# ME433.net
KiCad netlist of a schematic drawn in EAGLE
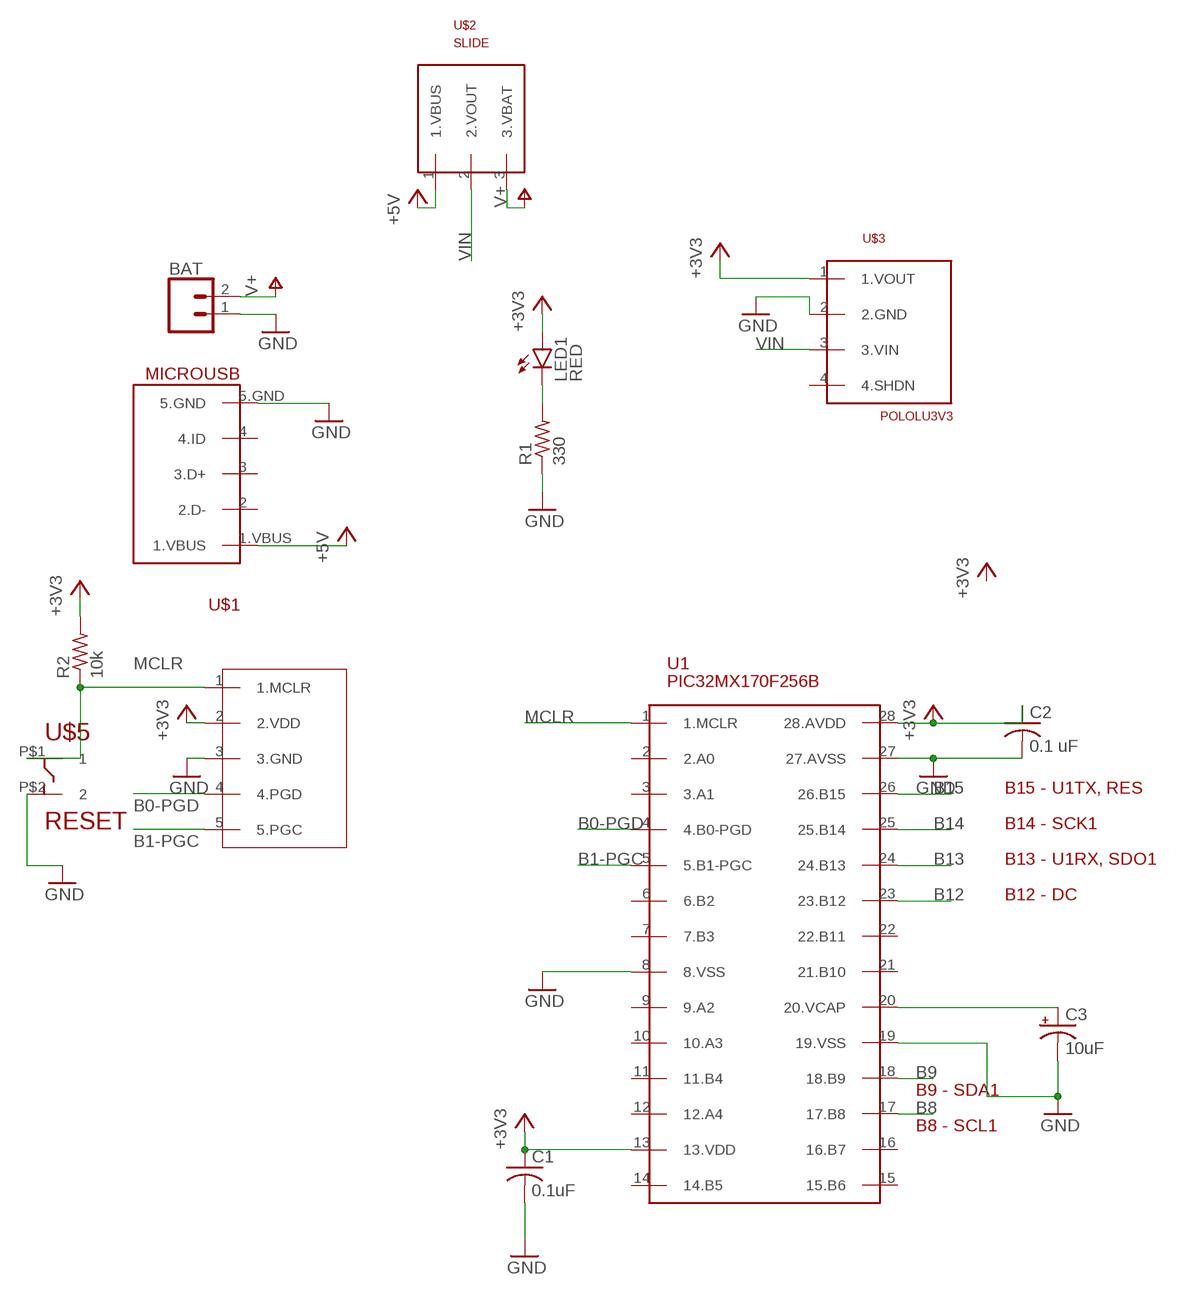
[diagram p0: schematic, sheet 1, part 1 of 2]
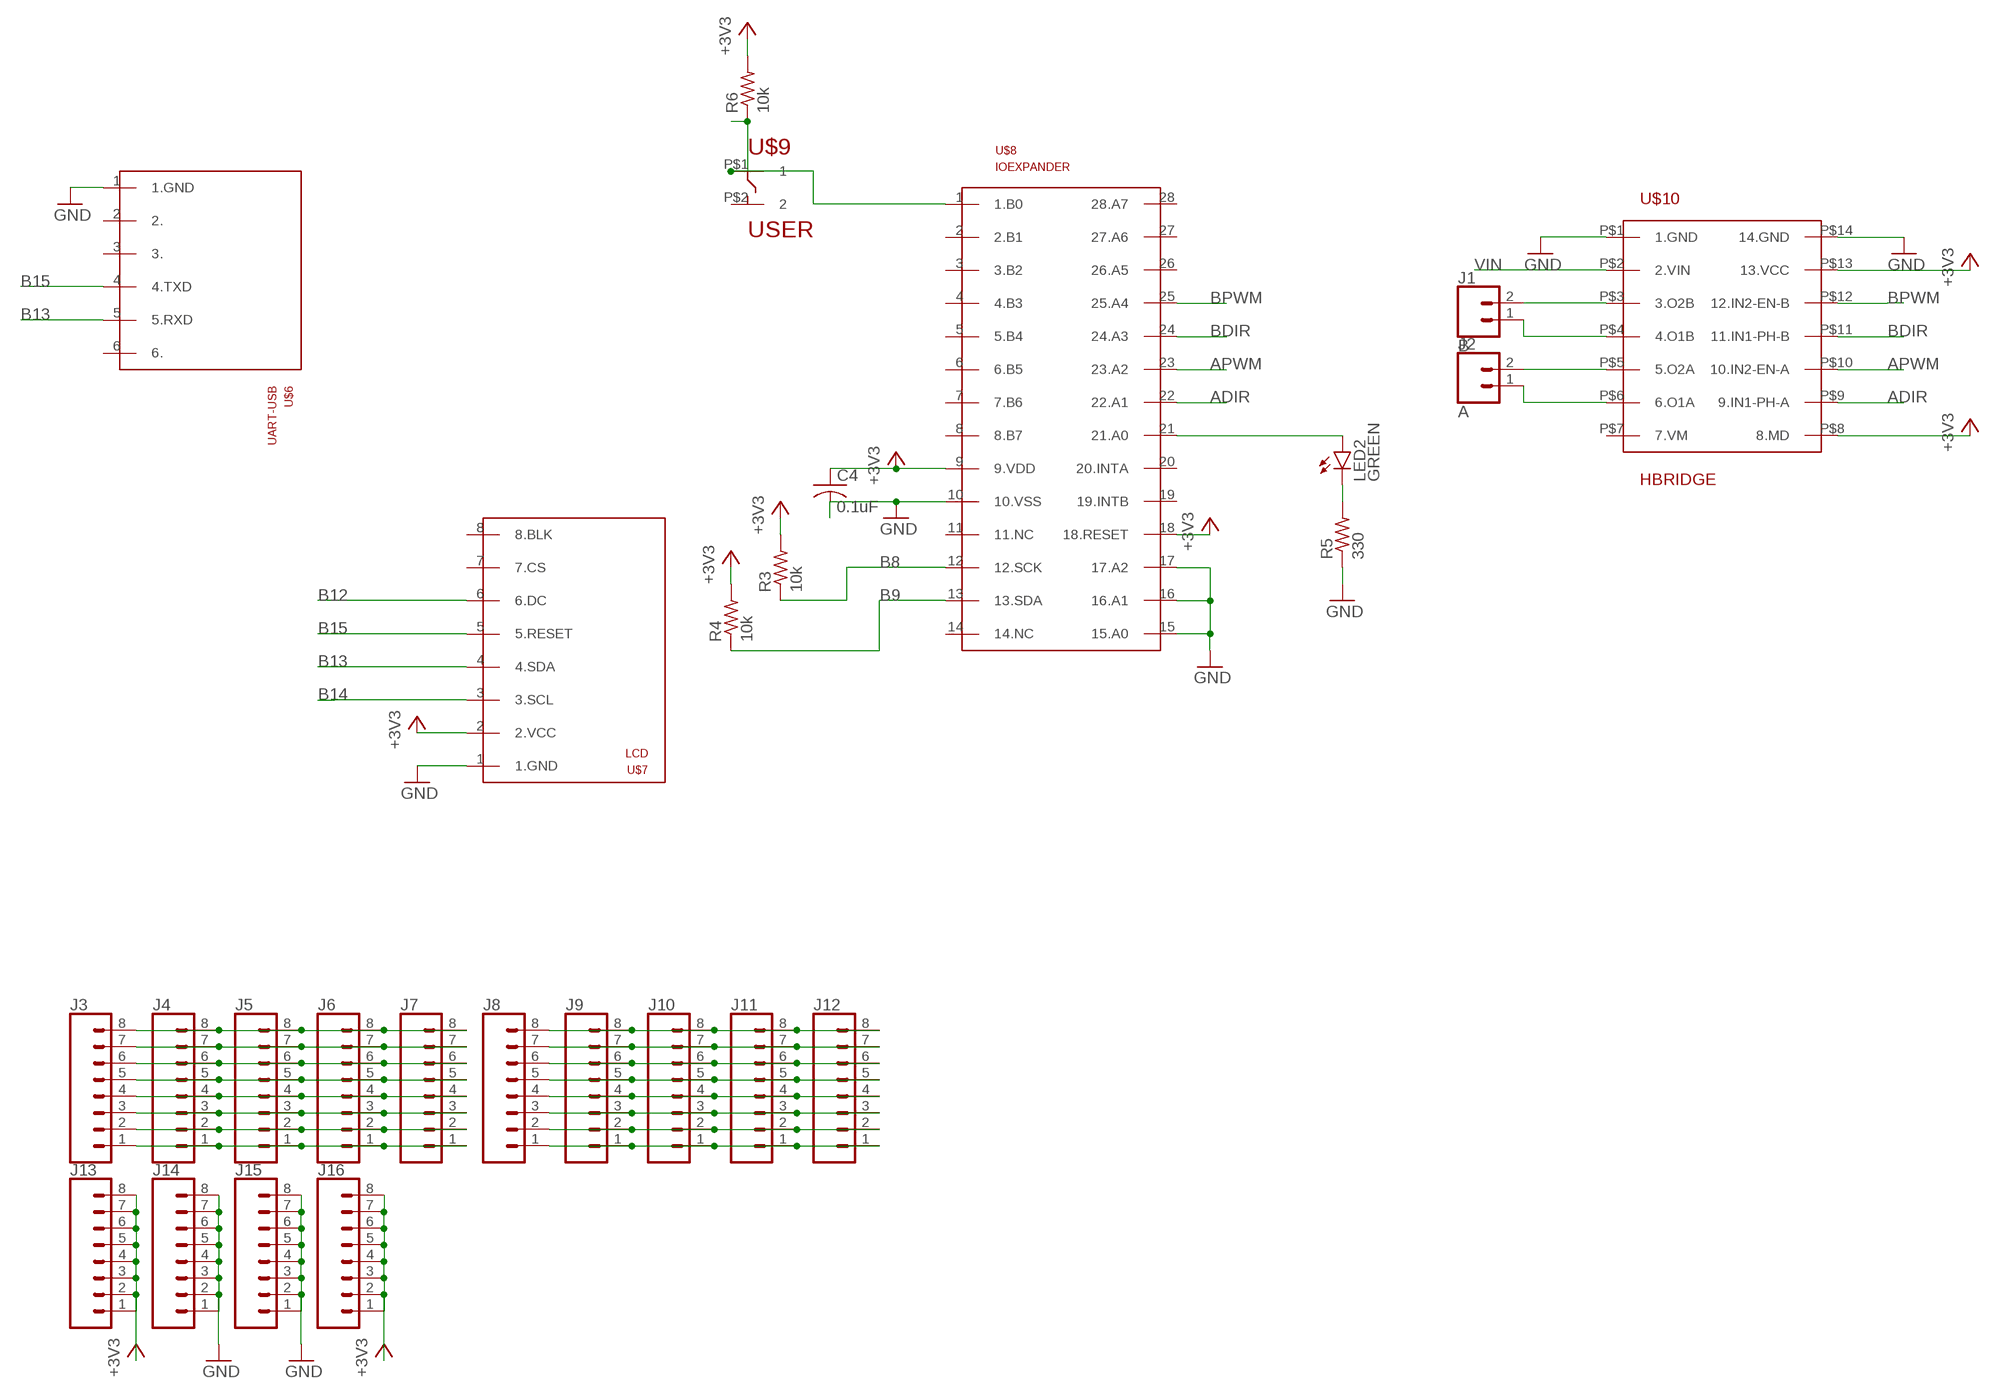
[diagram p1: schematic, sheet 1, part 2 of 2]

(export (version "E")
  (design (tool "Eeschema 10.0.6"))
  (components
    (comp (ref "BAT")
      (value "CONN_02")
      (footprint "eagle-import:1X02")
      (libsource (lib "eagle-import") (part "CONN_02"))
    )
    (comp (ref "C1")
      (value "0.1uF")
      (footprint "eagle-import:C025-030X050")
      (libsource (lib "eagle-import") (part "C-US025-030X050"))
    )
    (comp (ref "C2")
      (value "0.1 uF")
      (footprint "eagle-import:C025-030X050")
      (libsource (lib "eagle-import") (part "C-US025-030X050"))
    )
    (comp (ref "C3")
      (value "10uF")
      (footprint "eagle-import:B45181A")
      (libsource (lib "eagle-import") (part "CPOL-USB45181A"))
    )
    (comp (ref "C4")
      (value "0.1uF")
      (footprint "eagle-import:C025-030X050")
      (libsource (lib "eagle-import") (part "C-US025-030X050"))
    )
    (comp (ref "J1")
      (value "B")
      (footprint "eagle-import:1X02")
      (libsource (lib "eagle-import") (part "CONN_02"))
    )
    (comp (ref "J2")
      (value "A")
      (footprint "eagle-import:1X02")
      (libsource (lib "eagle-import") (part "CONN_02"))
    )
    (comp (ref "J3")
      (value "CONN_08\"")
      (footprint "eagle-import:1X08")
      (libsource (lib "eagle-import") (part "CONN_08{dblquote}"))
    )
    (comp (ref "J4")
      (value "CONN_08\"")
      (footprint "eagle-import:1X08")
      (libsource (lib "eagle-import") (part "CONN_08{dblquote}"))
    )
    (comp (ref "J5")
      (value "CONN_08\"")
      (footprint "eagle-import:1X08")
      (libsource (lib "eagle-import") (part "CONN_08{dblquote}"))
    )
    (comp (ref "J6")
      (value "CONN_08\"")
      (footprint "eagle-import:1X08")
      (libsource (lib "eagle-import") (part "CONN_08{dblquote}"))
    )
    (comp (ref "J7")
      (value "CONN_08\"")
      (footprint "eagle-import:1X08")
      (libsource (lib "eagle-import") (part "CONN_08{dblquote}"))
    )
    (comp (ref "J8")
      (value "CONN_08\"")
      (footprint "eagle-import:1X08")
      (libsource (lib "eagle-import") (part "CONN_08{dblquote}"))
    )
    (comp (ref "J9")
      (value "CONN_08\"")
      (footprint "eagle-import:1X08")
      (libsource (lib "eagle-import") (part "CONN_08{dblquote}"))
    )
    (comp (ref "J10")
      (value "CONN_08\"")
      (footprint "eagle-import:1X08")
      (libsource (lib "eagle-import") (part "CONN_08{dblquote}"))
    )
    (comp (ref "J11")
      (value "CONN_08\"")
      (footprint "eagle-import:1X08")
      (libsource (lib "eagle-import") (part "CONN_08{dblquote}"))
    )
    (comp (ref "J12")
      (value "CONN_08\"")
      (footprint "eagle-import:1X08")
      (libsource (lib "eagle-import") (part "CONN_08{dblquote}"))
    )
    (comp (ref "J13")
      (value "CONN_08\"")
      (footprint "eagle-import:1X08")
      (libsource (lib "eagle-import") (part "CONN_08{dblquote}"))
    )
    (comp (ref "J14")
      (value "CONN_08\"")
      (footprint "eagle-import:1X08")
      (libsource (lib "eagle-import") (part "CONN_08{dblquote}"))
    )
    (comp (ref "J15")
      (value "CONN_08\"")
      (footprint "eagle-import:1X08")
      (libsource (lib "eagle-import") (part "CONN_08{dblquote}"))
    )
    (comp (ref "J16")
      (value "CONN_08\"")
      (footprint "eagle-import:1X08")
      (libsource (lib "eagle-import") (part "CONN_08{dblquote}"))
    )
    (comp (ref "LED1")
      (value "RED")
      (footprint "eagle-import:LED3MM")
      (libsource (lib "eagle-import") (part "LED3MM"))
    )
    (comp (ref "LED2")
      (value "GREEN")
      (footprint "eagle-import:LED3MM")
      (libsource (lib "eagle-import") (part "LED3MM"))
    )
    (comp (ref "R1")
      (value "330")
      (footprint "eagle-import:0207_10")
      (libsource (lib "eagle-import") (part "R-US_0207/10"))
    )
    (comp (ref "R2")
      (value "10k")
      (footprint "eagle-import:0207_10")
      (libsource (lib "eagle-import") (part "R-US_0207/10"))
    )
    (comp (ref "R3")
      (value "10k")
      (footprint "eagle-import:0207_10")
      (libsource (lib "eagle-import") (part "R-US_0207/10"))
    )
    (comp (ref "R4")
      (value "10k")
      (footprint "eagle-import:0207_10")
      (libsource (lib "eagle-import") (part "R-US_0207/10"))
    )
    (comp (ref "R5")
      (value "330")
      (footprint "eagle-import:0207_10")
      (libsource (lib "eagle-import") (part "R-US_0207/10"))
    )
    (comp (ref "R6")
      (value "10k")
      (footprint "eagle-import:0207_10")
      (libsource (lib "eagle-import") (part "R-US_0207/10"))
    )
    (comp (ref "U$1")
      (value "MICROUSB")
      (footprint "eagle-import:MICROUSB")
      (libsource (lib "eagle-import") (part "MICROUSB"))
    )
    (comp (ref "U$2")
      (value "SLIDE")
      (footprint "eagle-import:SLIDE")
      (libsource (lib "eagle-import") (part "SLIDE"))
    )
    (comp (ref "U$3")
      (value "POLOLU3V3")
      (footprint "eagle-import:POLOLU3V3")
      (libsource (lib "eagle-import") (part "POLOLU3V3"))
    )
    (comp (ref "U$4")
      (value "SNAP")
      (footprint "eagle-import:SNAP")
      (libsource (lib "eagle-import") (part "SNAP"))
    )
    (comp (ref "U$5")
      (value "RESET")
      (footprint "eagle-import:PUSH")
      (libsource (lib "eagle-import") (part "PUSH"))
    )
    (comp (ref "U$6")
      (value "UART-USB")
      (footprint "eagle-import:UART-USB")
      (libsource (lib "eagle-import") (part "UART-USB"))
    )
    (comp (ref "U$7")
      (value "LCD")
      (footprint "eagle-import:LCD")
      (libsource (lib "eagle-import") (part "LCD"))
    )
    (comp (ref "U$8")
      (value "IOEXPANDER")
      (footprint "eagle-import:IOEXPANDER")
      (libsource (lib "eagle-import") (part "IOEXPANDER"))
    )
    (comp (ref "U$9")
      (value "USER")
      (footprint "eagle-import:PUSH")
      (libsource (lib "eagle-import") (part "PUSH"))
    )
    (comp (ref "U$10")
      (value "HBRIDGE")
      (footprint "eagle-import:HBRIDGE")
      (libsource (lib "eagle-import") (part "HBRIDGE"))
    )
    (comp (ref "U1")
      (value "PIC32MX170F256B")
      (footprint "eagle-import:DIL28-3")
      (libsource (lib "eagle-import") (part "PIC32MX170F256B"))
    )
  )
  (nets
    (net (code "1") (name "+3V3") (class "Default")
      (node (ref "C1") (pin "1") (pinfunction "1_1") (pintype "passive"))
      (node (ref "C2") (pin "1") (pinfunction "1_1") (pintype "passive"))
      (node (ref "C4") (pin "1") (pinfunction "1_1") (pintype "passive"))
      (node (ref "J13") (pin "1") (pinfunction "1_1") (pintype "passive"))
      (node (ref "J13") (pin "2") (pinfunction "2_2") (pintype "passive"))
      (node (ref "J13") (pin "3") (pinfunction "3_3") (pintype "passive"))
      (node (ref "J13") (pin "4") (pinfunction "4_4") (pintype "passive"))
      (node (ref "J13") (pin "5") (pinfunction "5_5") (pintype "passive"))
      (node (ref "J13") (pin "6") (pinfunction "6_6") (pintype "passive"))
      (node (ref "J13") (pin "7") (pinfunction "7_7") (pintype "passive"))
      (node (ref "J13") (pin "8") (pinfunction "8_8") (pintype "passive"))
      (node (ref "J16") (pin "1") (pinfunction "1_1") (pintype "passive"))
      (node (ref "J16") (pin "2") (pinfunction "2_2") (pintype "passive"))
      (node (ref "J16") (pin "3") (pinfunction "3_3") (pintype "passive"))
      (node (ref "J16") (pin "4") (pinfunction "4_4") (pintype "passive"))
      (node (ref "J16") (pin "5") (pinfunction "5_5") (pintype "passive"))
      (node (ref "J16") (pin "6") (pinfunction "6_6") (pintype "passive"))
      (node (ref "J16") (pin "7") (pinfunction "7_7") (pintype "passive"))
      (node (ref "J16") (pin "8") (pinfunction "8_8") (pintype "passive"))
      (node (ref "LED1") (pin "A") (pinfunction "A_A") (pintype "passive"))
      (node (ref "R2") (pin "2") (pinfunction "2_2") (pintype "passive"))
      (node (ref "R3") (pin "2") (pinfunction "2_2") (pintype "passive"))
      (node (ref "R4") (pin "2") (pinfunction "2_2") (pintype "passive"))
      (node (ref "R6") (pin "2") (pinfunction "2_2") (pintype "passive"))
      (node (ref "U$10") (pin "P$13") (pinfunction "13.VCC_P$13") (pintype "bidirectional"))
      (node (ref "U$10") (pin "P$8") (pinfunction "8.MD_P$8") (pintype "bidirectional"))
      (node (ref "U$3") (pin "1") (pinfunction "1.VOUT_1") (pintype "bidirectional"))
      (node (ref "U$4") (pin "2") (pinfunction "2.VDD_2") (pintype "bidirectional"))
      (node (ref "U$7") (pin "2") (pinfunction "2.VCC_2") (pintype "bidirectional"))
      (node (ref "U$8") (pin "18") (pinfunction "18.RESET_18") (pintype "bidirectional"))
      (node (ref "U$8") (pin "9") (pinfunction "9.VDD_9") (pintype "bidirectional"))
      (node (ref "U1") (pin "13") (pinfunction "13.VDD_13") (pintype "bidirectional"))
      (node (ref "U1") (pin "28") (pinfunction "28.AVDD_28") (pintype "bidirectional"))
    )
    (net (code "2") (name "+5V") (class "Default")
      (node (ref "U$1") (pin "1.VBUS") (pinfunction "1.VBUS_1.VBUS") (pintype "bidirectional"))
      (node (ref "U$2") (pin "1") (pinfunction "1.VBUS_1") (pintype "bidirectional"))
    )
    (net (code "3") (name "/ADIR") (class "Default")
      (node (ref "U$10") (pin "P$9") (pinfunction "9.IN1-PH-A_P$9") (pintype "bidirectional"))
      (node (ref "U$8") (pin "22") (pinfunction "22.A1_22") (pintype "bidirectional"))
    )
    (net (code "4") (name "/APWM") (class "Default")
      (node (ref "U$10") (pin "P$10") (pinfunction "10.IN2-EN-A_P$10") (pintype "bidirectional"))
      (node (ref "U$8") (pin "23") (pinfunction "23.A2_23") (pintype "bidirectional"))
    )
    (net (code "5") (name "/B0-PGD") (class "Default")
      (node (ref "U$4") (pin "4") (pinfunction "4.PGD_4") (pintype "bidirectional"))
      (node (ref "U1") (pin "4") (pinfunction "4.B0-PGD_4") (pintype "bidirectional"))
    )
    (net (code "6") (name "/B1-PGC") (class "Default")
      (node (ref "U$4") (pin "5") (pinfunction "5.PGC_5") (pintype "bidirectional"))
      (node (ref "U1") (pin "5") (pinfunction "5.B1-PGC_5") (pintype "bidirectional"))
    )
    (net (code "7") (name "/B8") (class "Default")
      (node (ref "R3") (pin "1") (pinfunction "1_1") (pintype "passive"))
      (node (ref "U$8") (pin "12") (pinfunction "12.SCK_12") (pintype "bidirectional"))
      (node (ref "U1") (pin "17") (pinfunction "17.B8_17") (pintype "bidirectional"))
    )
    (net (code "8") (name "/B9") (class "Default")
      (node (ref "R4") (pin "1") (pinfunction "1_1") (pintype "passive"))
      (node (ref "U$8") (pin "13") (pinfunction "13.SDA_13") (pintype "bidirectional"))
      (node (ref "U1") (pin "18") (pinfunction "18.B9_18") (pintype "bidirectional"))
    )
    (net (code "9") (name "/B12") (class "Default")
      (node (ref "U$7") (pin "6") (pinfunction "6.DC_6") (pintype "bidirectional"))
      (node (ref "U1") (pin "23") (pinfunction "23.B12_23") (pintype "bidirectional"))
    )
    (net (code "10") (name "/B13") (class "Default")
      (node (ref "U$6") (pin "5") (pinfunction "5.RXD_5") (pintype "bidirectional"))
      (node (ref "U$7") (pin "4") (pinfunction "4.SDA_4") (pintype "bidirectional"))
      (node (ref "U1") (pin "24") (pinfunction "24.B13_24") (pintype "bidirectional"))
    )
    (net (code "11") (name "/B14") (class "Default")
      (node (ref "U$7") (pin "3") (pinfunction "3.SCL_3") (pintype "bidirectional"))
      (node (ref "U1") (pin "25") (pinfunction "25.B14_25") (pintype "bidirectional"))
    )
    (net (code "12") (name "/B15") (class "Default")
      (node (ref "U$6") (pin "4") (pinfunction "4.TXD_4") (pintype "bidirectional"))
      (node (ref "U$7") (pin "5") (pinfunction "5.RESET_5") (pintype "bidirectional"))
      (node (ref "U1") (pin "26") (pinfunction "26.B15_26") (pintype "bidirectional"))
    )
    (net (code "13") (name "/BDIR") (class "Default")
      (node (ref "U$10") (pin "P$11") (pinfunction "11.IN1-PH-B_P$11") (pintype "bidirectional"))
      (node (ref "U$8") (pin "24") (pinfunction "24.A3_24") (pintype "bidirectional"))
    )
    (net (code "14") (name "/BPWM") (class "Default")
      (node (ref "U$10") (pin "P$12") (pinfunction "12.IN2-EN-B_P$12") (pintype "bidirectional"))
      (node (ref "U$8") (pin "25") (pinfunction "25.A4_25") (pintype "bidirectional"))
    )
    (net (code "15") (name "/MCLR") (class "Default")
      (node (ref "R2") (pin "1") (pinfunction "1_1") (pintype "passive"))
      (node (ref "U$4") (pin "1") (pinfunction "1.MCLR_1") (pintype "bidirectional"))
      (node (ref "U$5") (pin "P$1") (pinfunction "1_P$1") (pintype "bidirectional"))
      (node (ref "U1") (pin "1") (pinfunction "1.MCLR_1") (pintype "bidirectional"))
    )
    (net (code "16") (name "/VIN") (class "Default")
      (node (ref "U$10") (pin "P$2") (pinfunction "2.VIN_P$2") (pintype "bidirectional"))
      (node (ref "U$2") (pin "2") (pinfunction "2.VOUT_2") (pintype "bidirectional"))
      (node (ref "U$3") (pin "3") (pinfunction "3.VIN_3") (pintype "bidirectional"))
    )
    (net (code "17") (name "GND") (class "Default")
      (node (ref "BAT") (pin "1") (pinfunction "1_1") (pintype "passive"))
      (node (ref "C1") (pin "2") (pinfunction "2_2") (pintype "passive"))
      (node (ref "C2") (pin "2") (pinfunction "2_2") (pintype "passive"))
      (node (ref "C3") (pin "-") (pinfunction "-_-") (pintype "passive"))
      (node (ref "C4") (pin "2") (pinfunction "2_2") (pintype "passive"))
      (node (ref "J14") (pin "1") (pinfunction "1_1") (pintype "passive"))
      (node (ref "J14") (pin "2") (pinfunction "2_2") (pintype "passive"))
      (node (ref "J14") (pin "3") (pinfunction "3_3") (pintype "passive"))
      (node (ref "J14") (pin "4") (pinfunction "4_4") (pintype "passive"))
      (node (ref "J14") (pin "5") (pinfunction "5_5") (pintype "passive"))
      (node (ref "J14") (pin "6") (pinfunction "6_6") (pintype "passive"))
      (node (ref "J14") (pin "7") (pinfunction "7_7") (pintype "passive"))
      (node (ref "J14") (pin "8") (pinfunction "8_8") (pintype "passive"))
      (node (ref "J15") (pin "1") (pinfunction "1_1") (pintype "passive"))
      (node (ref "J15") (pin "2") (pinfunction "2_2") (pintype "passive"))
      (node (ref "J15") (pin "3") (pinfunction "3_3") (pintype "passive"))
      (node (ref "J15") (pin "4") (pinfunction "4_4") (pintype "passive"))
      (node (ref "J15") (pin "5") (pinfunction "5_5") (pintype "passive"))
      (node (ref "J15") (pin "6") (pinfunction "6_6") (pintype "passive"))
      (node (ref "J15") (pin "7") (pinfunction "7_7") (pintype "passive"))
      (node (ref "J15") (pin "8") (pinfunction "8_8") (pintype "passive"))
      (node (ref "R1") (pin "1") (pinfunction "1_1") (pintype "passive"))
      (node (ref "R5") (pin "1") (pinfunction "1_1") (pintype "passive"))
      (node (ref "U$1") (pin "5.GND") (pinfunction "5.GND_5.GND") (pintype "bidirectional"))
      (node (ref "U$10") (pin "P$1") (pinfunction "1.GND_P$1") (pintype "bidirectional"))
      (node (ref "U$10") (pin "P$14") (pinfunction "14.GND_P$14") (pintype "bidirectional"))
      (node (ref "U$3") (pin "2") (pinfunction "2.GND_2") (pintype "bidirectional"))
      (node (ref "U$4") (pin "3") (pinfunction "3.GND_3") (pintype "bidirectional"))
      (node (ref "U$5") (pin "P$2") (pinfunction "2_P$2") (pintype "bidirectional"))
      (node (ref "U$6") (pin "1") (pinfunction "1.GND_1") (pintype "bidirectional"))
      (node (ref "U$7") (pin "1") (pinfunction "1.GND_1") (pintype "bidirectional"))
      (node (ref "U$8") (pin "10") (pinfunction "10.VSS_10") (pintype "bidirectional"))
      (node (ref "U$8") (pin "15") (pinfunction "15.A0_15") (pintype "bidirectional"))
      (node (ref "U$8") (pin "16") (pinfunction "16.A1_16") (pintype "bidirectional"))
      (node (ref "U$8") (pin "17") (pinfunction "17.A2_17") (pintype "bidirectional"))
      (node (ref "U1") (pin "19") (pinfunction "19.VSS_19") (pintype "bidirectional"))
      (node (ref "U1") (pin "27") (pinfunction "27.AVSS_27") (pintype "bidirectional"))
      (node (ref "U1") (pin "8") (pinfunction "8.VSS_8") (pintype "bidirectional"))
    )
    (net (code "18") (name "Net-(J3-Pad1)") (class "Default")
      (node (ref "J3") (pin "1") (pinfunction "1_1") (pintype "passive"))
      (node (ref "J4") (pin "1") (pinfunction "1_1") (pintype "passive"))
      (node (ref "J5") (pin "1") (pinfunction "1_1") (pintype "passive"))
      (node (ref "J6") (pin "1") (pinfunction "1_1") (pintype "passive"))
      (node (ref "J7") (pin "1") (pinfunction "1_1") (pintype "passive"))
    )
    (net (code "19") (name "Net-(J3-Pad2)") (class "Default")
      (node (ref "J3") (pin "2") (pinfunction "2_2") (pintype "passive"))
      (node (ref "J4") (pin "2") (pinfunction "2_2") (pintype "passive"))
      (node (ref "J5") (pin "2") (pinfunction "2_2") (pintype "passive"))
      (node (ref "J6") (pin "2") (pinfunction "2_2") (pintype "passive"))
      (node (ref "J7") (pin "2") (pinfunction "2_2") (pintype "passive"))
    )
    (net (code "20") (name "Net-(J3-Pad3)") (class "Default")
      (node (ref "J3") (pin "3") (pinfunction "3_3") (pintype "passive"))
      (node (ref "J4") (pin "3") (pinfunction "3_3") (pintype "passive"))
      (node (ref "J5") (pin "3") (pinfunction "3_3") (pintype "passive"))
      (node (ref "J6") (pin "3") (pinfunction "3_3") (pintype "passive"))
      (node (ref "J7") (pin "3") (pinfunction "3_3") (pintype "passive"))
    )
    (net (code "21") (name "Net-(J3-Pad4)") (class "Default")
      (node (ref "J3") (pin "4") (pinfunction "4_4") (pintype "passive"))
      (node (ref "J4") (pin "4") (pinfunction "4_4") (pintype "passive"))
      (node (ref "J5") (pin "4") (pinfunction "4_4") (pintype "passive"))
      (node (ref "J6") (pin "4") (pinfunction "4_4") (pintype "passive"))
      (node (ref "J7") (pin "4") (pinfunction "4_4") (pintype "passive"))
    )
    (net (code "22") (name "Net-(J3-Pad5)") (class "Default")
      (node (ref "J3") (pin "5") (pinfunction "5_5") (pintype "passive"))
      (node (ref "J4") (pin "5") (pinfunction "5_5") (pintype "passive"))
      (node (ref "J5") (pin "5") (pinfunction "5_5") (pintype "passive"))
      (node (ref "J6") (pin "5") (pinfunction "5_5") (pintype "passive"))
      (node (ref "J7") (pin "5") (pinfunction "5_5") (pintype "passive"))
    )
    (net (code "23") (name "Net-(J3-Pad6)") (class "Default")
      (node (ref "J3") (pin "6") (pinfunction "6_6") (pintype "passive"))
      (node (ref "J4") (pin "6") (pinfunction "6_6") (pintype "passive"))
      (node (ref "J5") (pin "6") (pinfunction "6_6") (pintype "passive"))
      (node (ref "J6") (pin "6") (pinfunction "6_6") (pintype "passive"))
      (node (ref "J7") (pin "6") (pinfunction "6_6") (pintype "passive"))
    )
    (net (code "24") (name "Net-(J3-Pad7)") (class "Default")
      (node (ref "J3") (pin "7") (pinfunction "7_7") (pintype "passive"))
      (node (ref "J4") (pin "7") (pinfunction "7_7") (pintype "passive"))
      (node (ref "J5") (pin "7") (pinfunction "7_7") (pintype "passive"))
      (node (ref "J6") (pin "7") (pinfunction "7_7") (pintype "passive"))
      (node (ref "J7") (pin "7") (pinfunction "7_7") (pintype "passive"))
    )
    (net (code "25") (name "Net-(J3-Pad8)") (class "Default")
      (node (ref "J3") (pin "8") (pinfunction "8_8") (pintype "passive"))
      (node (ref "J4") (pin "8") (pinfunction "8_8") (pintype "passive"))
      (node (ref "J5") (pin "8") (pinfunction "8_8") (pintype "passive"))
      (node (ref "J6") (pin "8") (pinfunction "8_8") (pintype "passive"))
      (node (ref "J7") (pin "8") (pinfunction "8_8") (pintype "passive"))
    )
    (net (code "26") (name "Net-(J10-Pad1)") (class "Default")
      (node (ref "J10") (pin "1") (pinfunction "1_1") (pintype "passive"))
      (node (ref "J11") (pin "1") (pinfunction "1_1") (pintype "passive"))
      (node (ref "J12") (pin "1") (pinfunction "1_1") (pintype "passive"))
      (node (ref "J8") (pin "1") (pinfunction "1_1") (pintype "passive"))
      (node (ref "J9") (pin "1") (pinfunction "1_1") (pintype "passive"))
    )
    (net (code "27") (name "Net-(J10-Pad2)") (class "Default")
      (node (ref "J10") (pin "2") (pinfunction "2_2") (pintype "passive"))
      (node (ref "J11") (pin "2") (pinfunction "2_2") (pintype "passive"))
      (node (ref "J12") (pin "2") (pinfunction "2_2") (pintype "passive"))
      (node (ref "J8") (pin "2") (pinfunction "2_2") (pintype "passive"))
      (node (ref "J9") (pin "2") (pinfunction "2_2") (pintype "passive"))
    )
    (net (code "28") (name "Net-(J10-Pad3)") (class "Default")
      (node (ref "J10") (pin "3") (pinfunction "3_3") (pintype "passive"))
      (node (ref "J11") (pin "3") (pinfunction "3_3") (pintype "passive"))
      (node (ref "J12") (pin "3") (pinfunction "3_3") (pintype "passive"))
      (node (ref "J8") (pin "3") (pinfunction "3_3") (pintype "passive"))
      (node (ref "J9") (pin "3") (pinfunction "3_3") (pintype "passive"))
    )
    (net (code "29") (name "Net-(J10-Pad4)") (class "Default")
      (node (ref "J10") (pin "4") (pinfunction "4_4") (pintype "passive"))
      (node (ref "J11") (pin "4") (pinfunction "4_4") (pintype "passive"))
      (node (ref "J12") (pin "4") (pinfunction "4_4") (pintype "passive"))
      (node (ref "J8") (pin "4") (pinfunction "4_4") (pintype "passive"))
      (node (ref "J9") (pin "4") (pinfunction "4_4") (pintype "passive"))
    )
    (net (code "30") (name "Net-(J10-Pad5)") (class "Default")
      (node (ref "J10") (pin "5") (pinfunction "5_5") (pintype "passive"))
      (node (ref "J11") (pin "5") (pinfunction "5_5") (pintype "passive"))
      (node (ref "J12") (pin "5") (pinfunction "5_5") (pintype "passive"))
      (node (ref "J8") (pin "5") (pinfunction "5_5") (pintype "passive"))
      (node (ref "J9") (pin "5") (pinfunction "5_5") (pintype "passive"))
    )
    (net (code "31") (name "Net-(J10-Pad6)") (class "Default")
      (node (ref "J10") (pin "6") (pinfunction "6_6") (pintype "passive"))
      (node (ref "J11") (pin "6") (pinfunction "6_6") (pintype "passive"))
      (node (ref "J12") (pin "6") (pinfunction "6_6") (pintype "passive"))
      (node (ref "J8") (pin "6") (pinfunction "6_6") (pintype "passive"))
      (node (ref "J9") (pin "6") (pinfunction "6_6") (pintype "passive"))
    )
    (net (code "32") (name "Net-(J10-Pad7)") (class "Default")
      (node (ref "J10") (pin "7") (pinfunction "7_7") (pintype "passive"))
      (node (ref "J11") (pin "7") (pinfunction "7_7") (pintype "passive"))
      (node (ref "J12") (pin "7") (pinfunction "7_7") (pintype "passive"))
      (node (ref "J8") (pin "7") (pinfunction "7_7") (pintype "passive"))
      (node (ref "J9") (pin "7") (pinfunction "7_7") (pintype "passive"))
    )
    (net (code "33") (name "Net-(J10-Pad8)") (class "Default")
      (node (ref "J10") (pin "8") (pinfunction "8_8") (pintype "passive"))
      (node (ref "J11") (pin "8") (pinfunction "8_8") (pintype "passive"))
      (node (ref "J12") (pin "8") (pinfunction "8_8") (pintype "passive"))
      (node (ref "J8") (pin "8") (pinfunction "8_8") (pintype "passive"))
      (node (ref "J9") (pin "8") (pinfunction "8_8") (pintype "passive"))
    )
    (net (code "34") (name "Net-(LED1-C)") (class "Default")
      (node (ref "LED1") (pin "K") (pinfunction "C_K") (pintype "passive"))
      (node (ref "R1") (pin "2") (pinfunction "2_2") (pintype "passive"))
    )
    (net (code "35") (name "Net-(LED2-C)") (class "Default")
      (node (ref "LED2") (pin "K") (pinfunction "C_K") (pintype "passive"))
      (node (ref "R5") (pin "2") (pinfunction "2_2") (pintype "passive"))
    )
    (net (code "36") (name "Net-(U$8-1.B0)") (class "Default")
      (node (ref "R6") (pin "1") (pinfunction "1_1") (pintype "passive"))
      (node (ref "U$8") (pin "1") (pinfunction "1.B0_1") (pintype "bidirectional"))
      (node (ref "U$9") (pin "P$1") (pinfunction "1_P$1") (pintype "bidirectional"))
    )
    (net (code "37") (name "Net-(U$8-21.A0)") (class "Default")
      (node (ref "LED2") (pin "A") (pinfunction "A_A") (pintype "passive"))
      (node (ref "U$8") (pin "21") (pinfunction "21.A0_21") (pintype "bidirectional"))
    )
    (net (code "38") (name "Net-(U$10-3.O2B)") (class "Default")
      (node (ref "J1") (pin "2") (pinfunction "2_2") (pintype "passive"))
      (node (ref "U$10") (pin "P$3") (pinfunction "3.O2B_P$3") (pintype "bidirectional"))
    )
    (net (code "39") (name "Net-(U$10-4.O1B)") (class "Default")
      (node (ref "J1") (pin "1") (pinfunction "1_1") (pintype "passive"))
      (node (ref "U$10") (pin "P$4") (pinfunction "4.O1B_P$4") (pintype "bidirectional"))
    )
    (net (code "40") (name "Net-(U$10-5.O2A)") (class "Default")
      (node (ref "J2") (pin "2") (pinfunction "2_2") (pintype "passive"))
      (node (ref "U$10") (pin "P$5") (pinfunction "5.O2A_P$5") (pintype "bidirectional"))
    )
    (net (code "41") (name "Net-(U$10-6.O1A)") (class "Default")
      (node (ref "J2") (pin "1") (pinfunction "1_1") (pintype "passive"))
      (node (ref "U$10") (pin "P$6") (pinfunction "6.O1A_P$6") (pintype "bidirectional"))
    )
    (net (code "42") (name "Net-(U1-20.VCAP)") (class "Default")
      (node (ref "C3") (pin "+") (pinfunction "+_+") (pintype "passive"))
      (node (ref "U1") (pin "20") (pinfunction "20.VCAP_20") (pintype "bidirectional"))
    )
    (net (code "43") (name "V+") (class "Default")
      (node (ref "BAT") (pin "2") (pinfunction "2_2") (pintype "passive"))
      (node (ref "U$2") (pin "3") (pinfunction "3.VBAT_3") (pintype "bidirectional"))
    )
    (net (code "44") (name "unconnected-(U$1-2.D--Pad2)") (class "Default")
      (node (ref "U$1") (pin "2") (pinfunction "2.D-_2") (pintype "bidirectional"))
    )
    (net (code "45") (name "unconnected-(U$1-3.D+-Pad3)") (class "Default")
      (node (ref "U$1") (pin "3") (pinfunction "3.D+_3") (pintype "bidirectional"))
    )
    (net (code "46") (name "unconnected-(U$1-4.ID-Pad4)") (class "Default")
      (node (ref "U$1") (pin "4") (pinfunction "4.ID_4") (pintype "bidirectional"))
    )
    (net (code "47") (name "unconnected-(U$3-4.SHDN-Pad4)") (class "Default")
      (node (ref "U$3") (pin "4") (pinfunction "4.SHDN_4") (pintype "bidirectional"))
    )
    (net (code "48") (name "unconnected-(U$6-2.-Pad2)") (class "Default")
      (node (ref "U$6") (pin "2") (pinfunction "2._2") (pintype "bidirectional"))
    )
    (net (code "49") (name "unconnected-(U$6-3.-Pad3)") (class "Default")
      (node (ref "U$6") (pin "3") (pinfunction "3._3") (pintype "bidirectional"))
    )
    (net (code "50") (name "unconnected-(U$6-6.-Pad6)") (class "Default")
      (node (ref "U$6") (pin "6") (pinfunction "6._6") (pintype "bidirectional"))
    )
    (net (code "51") (name "unconnected-(U$7-7.CS-Pad7)") (class "Default")
      (node (ref "U$7") (pin "7") (pinfunction "7.CS_7") (pintype "bidirectional"))
    )
    (net (code "52") (name "unconnected-(U$7-8.BLK-Pad8)") (class "Default")
      (node (ref "U$7") (pin "8") (pinfunction "8.BLK_8") (pintype "bidirectional"))
    )
    (net (code "53") (name "unconnected-(U$8-2.B1-Pad2)") (class "Default")
      (node (ref "U$8") (pin "2") (pinfunction "2.B1_2") (pintype "bidirectional"))
    )
    (net (code "54") (name "unconnected-(U$8-3.B2-Pad3)") (class "Default")
      (node (ref "U$8") (pin "3") (pinfunction "3.B2_3") (pintype "bidirectional"))
    )
    (net (code "55") (name "unconnected-(U$8-4.B3-Pad4)") (class "Default")
      (node (ref "U$8") (pin "4") (pinfunction "4.B3_4") (pintype "bidirectional"))
    )
    (net (code "56") (name "unconnected-(U$8-5.B4-Pad5)") (class "Default")
      (node (ref "U$8") (pin "5") (pinfunction "5.B4_5") (pintype "bidirectional"))
    )
    (net (code "57") (name "unconnected-(U$8-6.B5-Pad6)") (class "Default")
      (node (ref "U$8") (pin "6") (pinfunction "6.B5_6") (pintype "bidirectional"))
    )
    (net (code "58") (name "unconnected-(U$8-7.B6-Pad7)") (class "Default")
      (node (ref "U$8") (pin "7") (pinfunction "7.B6_7") (pintype "bidirectional"))
    )
    (net (code "59") (name "unconnected-(U$8-8.B7-Pad8)") (class "Default")
      (node (ref "U$8") (pin "8") (pinfunction "8.B7_8") (pintype "bidirectional"))
    )
    (net (code "60") (name "unconnected-(U$8-11.NC-Pad11)") (class "Default")
      (node (ref "U$8") (pin "11") (pinfunction "11.NC_11") (pintype "bidirectional"))
    )
    (net (code "61") (name "unconnected-(U$8-14.NC-Pad14)") (class "Default")
      (node (ref "U$8") (pin "14") (pinfunction "14.NC_14") (pintype "bidirectional"))
    )
    (net (code "62") (name "unconnected-(U$8-19.INTB-Pad19)") (class "Default")
      (node (ref "U$8") (pin "19") (pinfunction "19.INTB_19") (pintype "bidirectional"))
    )
    (net (code "63") (name "unconnected-(U$8-20.INTA-Pad20)") (class "Default")
      (node (ref "U$8") (pin "20") (pinfunction "20.INTA_20") (pintype "bidirectional"))
    )
    (net (code "64") (name "unconnected-(U$8-26.A5-Pad26)") (class "Default")
      (node (ref "U$8") (pin "26") (pinfunction "26.A5_26") (pintype "bidirectional"))
    )
    (net (code "65") (name "unconnected-(U$8-27.A6-Pad27)") (class "Default")
      (node (ref "U$8") (pin "27") (pinfunction "27.A6_27") (pintype "bidirectional"))
    )
    (net (code "66") (name "unconnected-(U$8-28.A7-Pad28)") (class "Default")
      (node (ref "U$8") (pin "28") (pinfunction "28.A7_28") (pintype "bidirectional"))
    )
    (net (code "67") (name "unconnected-(U$9-2-PadP$2)") (class "Default")
      (node (ref "U$9") (pin "P$2") (pinfunction "2_P$2") (pintype "bidirectional"))
    )
    (net (code "68") (name "unconnected-(U$10-7.VM-PadP$7)") (class "Default")
      (node (ref "U$10") (pin "P$7") (pinfunction "7.VM_P$7") (pintype "bidirectional"))
    )
    (net (code "69") (name "unconnected-(U1-2.A0-Pad2)") (class "Default")
      (node (ref "U1") (pin "2") (pinfunction "2.A0_2") (pintype "bidirectional"))
    )
    (net (code "70") (name "unconnected-(U1-3.A1-Pad3)") (class "Default")
      (node (ref "U1") (pin "3") (pinfunction "3.A1_3") (pintype "bidirectional"))
    )
    (net (code "71") (name "unconnected-(U1-6.B2-Pad6)") (class "Default")
      (node (ref "U1") (pin "6") (pinfunction "6.B2_6") (pintype "bidirectional"))
    )
    (net (code "72") (name "unconnected-(U1-7.B3-Pad7)") (class "Default")
      (node (ref "U1") (pin "7") (pinfunction "7.B3_7") (pintype "bidirectional"))
    )
    (net (code "73") (name "unconnected-(U1-9.A2-Pad9)") (class "Default")
      (node (ref "U1") (pin "9") (pinfunction "9.A2_9") (pintype "bidirectional"))
    )
    (net (code "74") (name "unconnected-(U1-10.A3-Pad10)") (class "Default")
      (node (ref "U1") (pin "10") (pinfunction "10.A3_10") (pintype "bidirectional"))
    )
    (net (code "75") (name "unconnected-(U1-11.B4-Pad11)") (class "Default")
      (node (ref "U1") (pin "11") (pinfunction "11.B4_11") (pintype "bidirectional"))
    )
    (net (code "76") (name "unconnected-(U1-12.A4-Pad12)") (class "Default")
      (node (ref "U1") (pin "12") (pinfunction "12.A4_12") (pintype "bidirectional"))
    )
    (net (code "77") (name "unconnected-(U1-14.B5-Pad14)") (class "Default")
      (node (ref "U1") (pin "14") (pinfunction "14.B5_14") (pintype "bidirectional"))
    )
    (net (code "78") (name "unconnected-(U1-15.B6-Pad15)") (class "Default")
      (node (ref "U1") (pin "15") (pinfunction "15.B6_15") (pintype "bidirectional"))
    )
    (net (code "79") (name "unconnected-(U1-16.B7-Pad16)") (class "Default")
      (node (ref "U1") (pin "16") (pinfunction "16.B7_16") (pintype "bidirectional"))
    )
    (net (code "80") (name "unconnected-(U1-21.B10-Pad21)") (class "Default")
      (node (ref "U1") (pin "21") (pinfunction "21.B10_21") (pintype "bidirectional"))
    )
    (net (code "81") (name "unconnected-(U1-22.B11-Pad22)") (class "Default")
      (node (ref "U1") (pin "22") (pinfunction "22.B11_22") (pintype "bidirectional"))
    )
  )
)
